# InterfazSpectrum.net
KiCad netlist of a schematic drawn in EAGLE
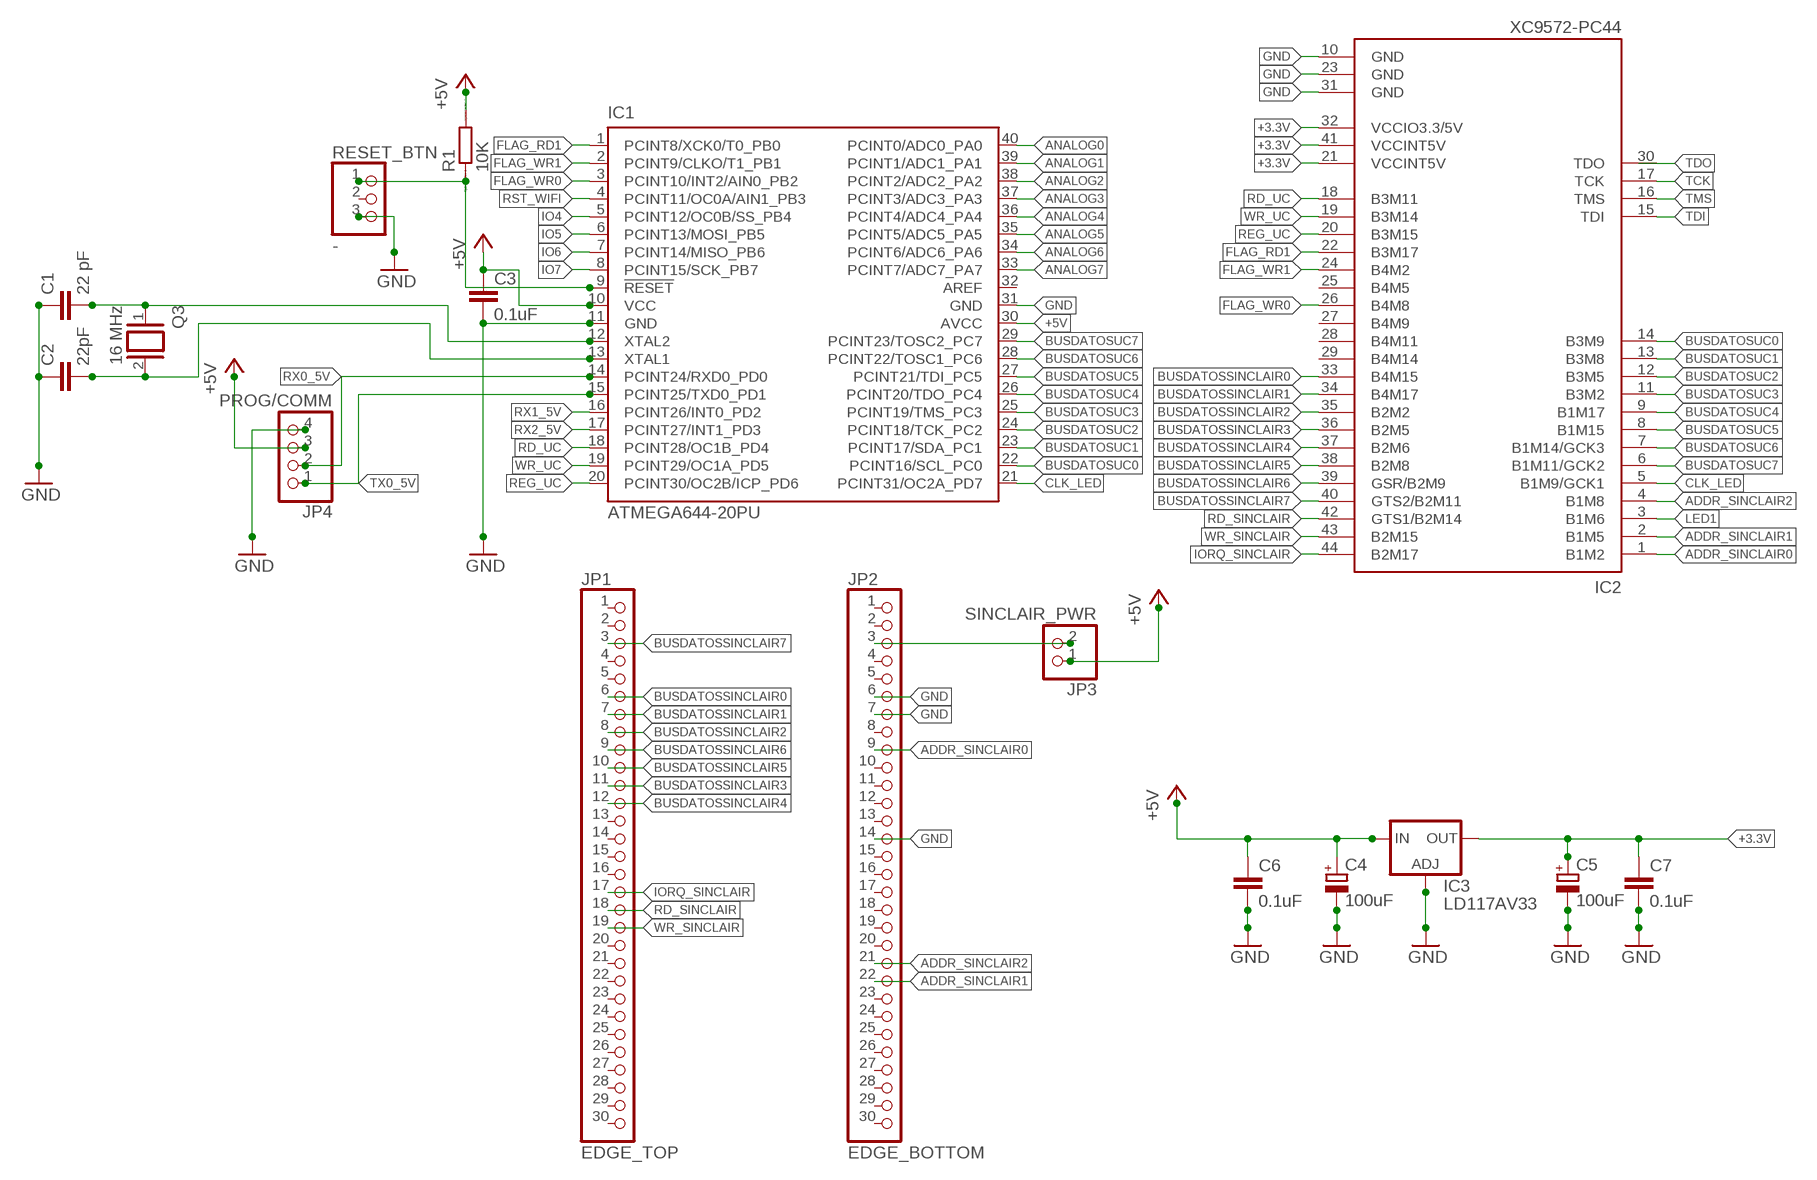
[diagram p0: schematic, sheet 1]

(export (version "E")
  (design (tool "Eeschema 10.0.6"))
  (components
    (comp (ref "C1")
      (value "22 pF")
      (footprint "eagle-import:C025-024X044")
      (libsource (lib "eagle-import") (part "C-EU025-024X044"))
    )
    (comp (ref "C2")
      (value "22pF")
      (footprint "eagle-import:C025-024X044")
      (libsource (lib "eagle-import") (part "C-EU025-024X044"))
    )
    (comp (ref "C3")
      (value "0.1uF")
      (footprint "eagle-import:C025-025X050")
      (libsource (lib "eagle-import") (part "C-EU025-025X050"))
    )
    (comp (ref "C4")
      (value "100uF")
      (footprint "eagle-import:E2,5-7")
      (libsource (lib "eagle-import") (part "CPOL-EUE2.5-7"))
    )
    (comp (ref "C5")
      (value "100uF")
      (footprint "eagle-import:E2,5-7")
      (libsource (lib "eagle-import") (part "CPOL-EUE2.5-7"))
    )
    (comp (ref "C6")
      (value "0.1uF")
      (footprint "eagle-import:C025-025X050")
      (libsource (lib "eagle-import") (part "C-EU025-025X050"))
    )
    (comp (ref "C7")
      (value "0.1uF")
      (footprint "eagle-import:C025-025X050")
      (libsource (lib "eagle-import") (part "C-EU025-025X050"))
    )
    (comp (ref "IC1")
      (value "ATMEGA644-20PU")
      (footprint "eagle-import:DIL40")
      (libsource (lib "eagle-import") (part "ATMEGA644-PU20"))
    )
    (comp (ref "IC2")
      (value "XC9572-PC44")
      (footprint "eagle-import:PLCC-S44")
      (libsource (lib "eagle-import") (part "XC9572-PC44"))
    )
    (comp (ref "IC3")
      (value "LD117AV33")
      (footprint "eagle-import:TO220L1")
      (libsource (lib "eagle-import") (part "LD117A?V33"))
    )
    (comp (ref "JP1")
      (value "EDGE_TOP")
      (footprint "eagle-import:1X30")
      (libsource (lib "eagle-import") (part "PINHD-1X30"))
    )
    (comp (ref "JP2")
      (value "EDGE_BOTTOM")
      (footprint "eagle-import:1X30")
      (libsource (lib "eagle-import") (part "PINHD-1X30"))
    )
    (comp (ref "JP3")
      (value "SINCLAIR_PWR")
      (footprint "eagle-import:1X02")
      (libsource (lib "eagle-import") (part "PINHD-1X2"))
    )
    (comp (ref "JP4")
      (value "PROG/COMM")
      (footprint "eagle-import:1X04")
      (libsource (lib "eagle-import") (part "PINHD-1X4"))
    )
    (comp (ref "Q3")
      (value "16 MHz")
      (footprint "eagle-import:QS")
      (libsource (lib "eagle-import") (part "XTAL/S"))
    )
    (comp (ref "R1")
      (value "10K")
      (footprint "eagle-import:0204V")
      (libsource (lib "eagle-import") (part "R-EU_0204_2V"))
    )
    (comp (ref "RESET_BTN")
      (value "-")
      (footprint "eagle-import:1X03")
      (libsource (lib "eagle-import") (part "PINHD-1X3"))
    )
  )
  (nets
    (net (code "1") (name "+3.3V") (class "Default")
      (node (ref "C5") (pin "+") (pinfunction "+_+") (pintype "passive"))
      (node (ref "C7") (pin "1") (pinfunction "1_1") (pintype "passive"))
      (node (ref "IC2") (pin "21") (pinfunction "VCCINT5V_21") (pintype "bidirectional"))
      (node (ref "IC2") (pin "32") (pinfunction "VCCIO3.3/5V_32") (pintype "bidirectional"))
      (node (ref "IC2") (pin "41") (pinfunction "VCCINT5V_41") (pintype "bidirectional"))
      (node (ref "IC3") (pin "2") (pinfunction "OUT_2") (pintype "passive"))
    )
    (net (code "2") (name "+5V") (class "Default")
      (node (ref "C3") (pin "1") (pinfunction "1_1") (pintype "passive"))
      (node (ref "C4") (pin "+") (pinfunction "+_+") (pintype "passive"))
      (node (ref "C6") (pin "1") (pinfunction "1_1") (pintype "passive"))
      (node (ref "IC1") (pin "10") (pinfunction "VCC_10") (pintype "power_in"))
      (node (ref "IC1") (pin "30") (pinfunction "AVCC_30") (pintype "power_in"))
      (node (ref "IC3") (pin "3") (pinfunction "IN_3") (pintype "input"))
      (node (ref "JP3") (pin "1") (pinfunction "1_1") (pintype "passive"))
      (node (ref "JP4") (pin "3") (pinfunction "3_3") (pintype "passive"))
      (node (ref "R1") (pin "2") (pinfunction "2_2") (pintype "passive"))
    )
    (net (code "3") (name "ADDR_SINCLAIR0") (class "Default")
      (node (ref "IC2") (pin "1") (pinfunction "B1M2_1") (pintype "bidirectional"))
      (node (ref "JP2") (pin "9") (pinfunction "9_9") (pintype "passive"))
    )
    (net (code "4") (name "ADDR_SINCLAIR1") (class "Default")
      (node (ref "IC2") (pin "2") (pinfunction "B1M5_2") (pintype "bidirectional"))
      (node (ref "JP2") (pin "22") (pinfunction "22_22") (pintype "passive"))
    )
    (net (code "5") (name "ADDR_SINCLAIR2") (class "Default")
      (node (ref "IC2") (pin "4") (pinfunction "B1M8_4") (pintype "bidirectional"))
      (node (ref "JP2") (pin "21") (pinfunction "21_21") (pintype "passive"))
    )
    (net (code "6") (name "ANALOG0") (class "Default")
      (node (ref "IC1") (pin "40") (pinfunction "PCINT0/ADC0_PA0_40") (pintype "bidirectional"))
    )
    (net (code "7") (name "ANALOG1") (class "Default")
      (node (ref "IC1") (pin "39") (pinfunction "PCINT1/ADC1_PA1_39") (pintype "bidirectional"))
    )
    (net (code "8") (name "ANALOG2") (class "Default")
      (node (ref "IC1") (pin "38") (pinfunction "PCINT2/ADC2_PA2_38") (pintype "bidirectional"))
    )
    (net (code "9") (name "ANALOG3") (class "Default")
      (node (ref "IC1") (pin "37") (pinfunction "PCINT3/ADC3_PA3_37") (pintype "bidirectional"))
    )
    (net (code "10") (name "ANALOG4") (class "Default")
      (node (ref "IC1") (pin "36") (pinfunction "PCINT4/ADC4_PA4_36") (pintype "bidirectional"))
    )
    (net (code "11") (name "ANALOG5") (class "Default")
      (node (ref "IC1") (pin "35") (pinfunction "PCINT5/ADC5_PA5_35") (pintype "bidirectional"))
    )
    (net (code "12") (name "ANALOG6") (class "Default")
      (node (ref "IC1") (pin "34") (pinfunction "PCINT6/ADC6_PA6_34") (pintype "bidirectional"))
    )
    (net (code "13") (name "ANALOG7") (class "Default")
      (node (ref "IC1") (pin "33") (pinfunction "PCINT7/ADC7_PA7_33") (pintype "bidirectional"))
    )
    (net (code "14") (name "BUSDATOSSINCLAIR0") (class "Default")
      (node (ref "IC2") (pin "33") (pinfunction "B4M15_33") (pintype "bidirectional"))
      (node (ref "JP1") (pin "6") (pinfunction "6_6") (pintype "passive"))
    )
    (net (code "15") (name "BUSDATOSSINCLAIR1") (class "Default")
      (node (ref "IC2") (pin "34") (pinfunction "B4M17_34") (pintype "bidirectional"))
      (node (ref "JP1") (pin "7") (pinfunction "7_7") (pintype "passive"))
    )
    (net (code "16") (name "BUSDATOSSINCLAIR2") (class "Default")
      (node (ref "IC2") (pin "35") (pinfunction "B2M2_35") (pintype "bidirectional"))
      (node (ref "JP1") (pin "8") (pinfunction "8_8") (pintype "passive"))
    )
    (net (code "17") (name "BUSDATOSSINCLAIR3") (class "Default")
      (node (ref "IC2") (pin "36") (pinfunction "B2M5_36") (pintype "bidirectional"))
      (node (ref "JP1") (pin "11") (pinfunction "11_11") (pintype "passive"))
    )
    (net (code "18") (name "BUSDATOSSINCLAIR4") (class "Default")
      (node (ref "IC2") (pin "37") (pinfunction "B2M6_37") (pintype "bidirectional"))
      (node (ref "JP1") (pin "12") (pinfunction "12_12") (pintype "passive"))
    )
    (net (code "19") (name "BUSDATOSSINCLAIR5") (class "Default")
      (node (ref "IC2") (pin "38") (pinfunction "B2M8_38") (pintype "bidirectional"))
      (node (ref "JP1") (pin "10") (pinfunction "10_10") (pintype "passive"))
    )
    (net (code "20") (name "BUSDATOSSINCLAIR6") (class "Default")
      (node (ref "IC2") (pin "39") (pinfunction "GSR/B2M9_39") (pintype "bidirectional"))
      (node (ref "JP1") (pin "9") (pinfunction "9_9") (pintype "passive"))
    )
    (net (code "21") (name "BUSDATOSSINCLAIR7") (class "Default")
      (node (ref "IC2") (pin "40") (pinfunction "GTS2/B2M11_40") (pintype "bidirectional"))
      (node (ref "JP1") (pin "3") (pinfunction "3_3") (pintype "passive"))
    )
    (net (code "22") (name "BUSDATOSUC0") (class "Default")
      (node (ref "IC1") (pin "22") (pinfunction "PCINT16/SCL_PC0_22") (pintype "bidirectional"))
      (node (ref "IC2") (pin "14") (pinfunction "B3M9_14") (pintype "bidirectional"))
    )
    (net (code "23") (name "BUSDATOSUC1") (class "Default")
      (node (ref "IC1") (pin "23") (pinfunction "PCINT17/SDA_PC1_23") (pintype "bidirectional"))
      (node (ref "IC2") (pin "13") (pinfunction "B3M8_13") (pintype "bidirectional"))
    )
    (net (code "24") (name "BUSDATOSUC2") (class "Default")
      (node (ref "IC1") (pin "24") (pinfunction "PCINT18/TCK_PC2_24") (pintype "bidirectional"))
      (node (ref "IC2") (pin "12") (pinfunction "B3M5_12") (pintype "bidirectional"))
    )
    (net (code "25") (name "BUSDATOSUC3") (class "Default")
      (node (ref "IC1") (pin "25") (pinfunction "PCINT19/TMS_PC3_25") (pintype "bidirectional"))
      (node (ref "IC2") (pin "11") (pinfunction "B3M2_11") (pintype "bidirectional"))
    )
    (net (code "26") (name "BUSDATOSUC4") (class "Default")
      (node (ref "IC1") (pin "26") (pinfunction "PCINT20/TDO_PC4_26") (pintype "bidirectional"))
      (node (ref "IC2") (pin "9") (pinfunction "B1M17_9") (pintype "bidirectional"))
    )
    (net (code "27") (name "BUSDATOSUC5") (class "Default")
      (node (ref "IC1") (pin "27") (pinfunction "PCINT21/TDI_PC5_27") (pintype "bidirectional"))
      (node (ref "IC2") (pin "8") (pinfunction "B1M15_8") (pintype "bidirectional"))
    )
    (net (code "28") (name "BUSDATOSUC6") (class "Default")
      (node (ref "IC1") (pin "28") (pinfunction "PCINT22/TOSC1_PC6_28") (pintype "bidirectional"))
      (node (ref "IC2") (pin "7") (pinfunction "B1M14/GCK3_7") (pintype "bidirectional"))
    )
    (net (code "29") (name "BUSDATOSUC7") (class "Default")
      (node (ref "IC1") (pin "29") (pinfunction "PCINT23/TOSC2_PC7_29") (pintype "bidirectional"))
      (node (ref "IC2") (pin "6") (pinfunction "B1M11/GCK2_6") (pintype "bidirectional"))
    )
    (net (code "30") (name "CLK_LED") (class "Default")
      (node (ref "IC1") (pin "21") (pinfunction "PCINT31/OC2A_PD7_21") (pintype "bidirectional"))
      (node (ref "IC2") (pin "5") (pinfunction "B1M9/GCK1_5") (pintype "bidirectional"))
    )
    (net (code "31") (name "FLAG_RD1") (class "Default")
      (node (ref "IC1") (pin "1") (pinfunction "PCINT8/XCK0/T0_PB0_1") (pintype "bidirectional"))
      (node (ref "IC2") (pin "22") (pinfunction "B3M17_22") (pintype "bidirectional"))
    )
    (net (code "32") (name "FLAG_WR0") (class "Default")
      (node (ref "IC1") (pin "3") (pinfunction "PCINT10/INT2/AIN0_PB2_3") (pintype "bidirectional"))
      (node (ref "IC2") (pin "26") (pinfunction "B4M8_26") (pintype "bidirectional"))
    )
    (net (code "33") (name "FLAG_WR1") (class "Default")
      (node (ref "IC1") (pin "2") (pinfunction "PCINT9/CLKO/T1_PB1_2") (pintype "bidirectional"))
      (node (ref "IC2") (pin "24") (pinfunction "B4M2_24") (pintype "bidirectional"))
    )
    (net (code "34") (name "GND") (class "Default")
      (node (ref "C1") (pin "1") (pinfunction "1_1") (pintype "passive"))
      (node (ref "C2") (pin "1") (pinfunction "1_1") (pintype "passive"))
      (node (ref "C3") (pin "2") (pinfunction "2_2") (pintype "passive"))
      (node (ref "C4") (pin "-") (pinfunction "-_-") (pintype "passive"))
      (node (ref "C5") (pin "-") (pinfunction "-_-") (pintype "passive"))
      (node (ref "C6") (pin "2") (pinfunction "2_2") (pintype "passive"))
      (node (ref "C7") (pin "2") (pinfunction "2_2") (pintype "passive"))
      (node (ref "IC1") (pin "11") (pinfunction "GND_11") (pintype "power_in"))
      (node (ref "IC1") (pin "31") (pinfunction "GND_31") (pintype "power_in"))
      (node (ref "IC2") (pin "10") (pinfunction "GND_10") (pintype "bidirectional"))
      (node (ref "IC2") (pin "23") (pinfunction "GND_23") (pintype "bidirectional"))
      (node (ref "IC2") (pin "31") (pinfunction "GND_31") (pintype "bidirectional"))
      (node (ref "IC3") (pin "1") (pinfunction "ADJ_1") (pintype "input"))
      (node (ref "JP2") (pin "14") (pinfunction "14_14") (pintype "passive"))
      (node (ref "JP2") (pin "6") (pinfunction "6_6") (pintype "passive"))
      (node (ref "JP2") (pin "7") (pinfunction "7_7") (pintype "passive"))
      (node (ref "JP4") (pin "4") (pinfunction "4_4") (pintype "passive"))
      (node (ref "RESET_BTN") (pin "3") (pinfunction "3_3") (pintype "passive"))
    )
    (net (code "35") (name "IO4") (class "Default")
      (node (ref "IC1") (pin "5") (pinfunction "PCINT12/OC0B/SS_PB4_5") (pintype "bidirectional"))
    )
    (net (code "36") (name "IO5") (class "Default")
      (node (ref "IC1") (pin "6") (pinfunction "PCINT13/MOSI_PB5_6") (pintype "bidirectional"))
    )
    (net (code "37") (name "IO6") (class "Default")
      (node (ref "IC1") (pin "7") (pinfunction "PCINT14/MISO_PB6_7") (pintype "bidirectional"))
    )
    (net (code "38") (name "IO7") (class "Default")
      (node (ref "IC1") (pin "8") (pinfunction "PCINT15/SCK_PB7_8") (pintype "bidirectional"))
    )
    (net (code "39") (name "IORQ_SINCLAIR") (class "Default")
      (node (ref "IC2") (pin "44") (pinfunction "B2M17_44") (pintype "bidirectional"))
      (node (ref "JP1") (pin "17") (pinfunction "17_17") (pintype "passive"))
    )
    (net (code "40") (name "LED1") (class "Default")
      (node (ref "IC2") (pin "3") (pinfunction "B1M6_3") (pintype "bidirectional"))
    )
    (net (code "41") (name "Net-(IC1-XTAL1)") (class "Default")
      (node (ref "C2") (pin "2") (pinfunction "2_2") (pintype "passive"))
      (node (ref "IC1") (pin "13") (pinfunction "XTAL1_13") (pintype "input"))
      (node (ref "Q3") (pin "2") (pinfunction "2_2") (pintype "passive"))
    )
    (net (code "42") (name "Net-(IC1-XTAL2)") (class "Default")
      (node (ref "C1") (pin "2") (pinfunction "2_2") (pintype "passive"))
      (node (ref "IC1") (pin "12") (pinfunction "XTAL2_12") (pintype "output"))
      (node (ref "Q3") (pin "1") (pinfunction "1_1") (pintype "passive"))
    )
    (net (code "43") (name "Net-(IC1-~{RESET})") (class "Default")
      (node (ref "IC1") (pin "9") (pinfunction "~{RESET}_9") (pintype "input"))
      (node (ref "R1") (pin "1") (pinfunction "1_1") (pintype "passive"))
      (node (ref "RESET_BTN") (pin "1") (pinfunction "1_1") (pintype "passive"))
    )
    (net (code "44") (name "Net-(JP2-Pad3)") (class "Default")
      (node (ref "JP2") (pin "3") (pinfunction "3_3") (pintype "passive"))
      (node (ref "JP3") (pin "2") (pinfunction "2_2") (pintype "passive"))
    )
    (net (code "45") (name "RD_SINCLAIR") (class "Default")
      (node (ref "IC2") (pin "42") (pinfunction "GTS1/B2M14_42") (pintype "bidirectional"))
      (node (ref "JP1") (pin "18") (pinfunction "18_18") (pintype "passive"))
    )
    (net (code "46") (name "RD_UC") (class "Default")
      (node (ref "IC1") (pin "18") (pinfunction "PCINT28/OC1B_PD4_18") (pintype "bidirectional"))
      (node (ref "IC2") (pin "18") (pinfunction "B3M11_18") (pintype "bidirectional"))
    )
    (net (code "47") (name "REG_UC") (class "Default")
      (node (ref "IC1") (pin "20") (pinfunction "PCINT30/OC2B/ICP_PD6_20") (pintype "bidirectional"))
      (node (ref "IC2") (pin "20") (pinfunction "B3M15_20") (pintype "bidirectional"))
    )
    (net (code "48") (name "RST_WIFI") (class "Default")
      (node (ref "IC1") (pin "4") (pinfunction "PCINT11/OC0A/AIN1_PB3_4") (pintype "bidirectional"))
    )
    (net (code "49") (name "RX0_5V") (class "Default")
      (node (ref "IC1") (pin "14") (pinfunction "PCINT24/RXD0_PD0_14") (pintype "bidirectional"))
      (node (ref "JP4") (pin "2") (pinfunction "2_2") (pintype "passive"))
    )
    (net (code "50") (name "RX1_5V") (class "Default")
      (node (ref "IC1") (pin "16") (pinfunction "PCINT26/INT0_PD2_16") (pintype "bidirectional"))
    )
    (net (code "51") (name "RX2_5V") (class "Default")
      (node (ref "IC1") (pin "17") (pinfunction "PCINT27/INT1_PD3_17") (pintype "bidirectional"))
    )
    (net (code "52") (name "TCK") (class "Default")
      (node (ref "IC2") (pin "17") (pinfunction "TCK_17") (pintype "bidirectional"))
    )
    (net (code "53") (name "TDI") (class "Default")
      (node (ref "IC2") (pin "15") (pinfunction "TDI_15") (pintype "bidirectional"))
    )
    (net (code "55") (name "TMS") (class "Default")
      (node (ref "IC2") (pin "16") (pinfunction "TMS_16") (pintype "bidirectional"))
    )
    (net (code "56") (name "TX0_5V") (class "Default")
      (node (ref "IC1") (pin "15") (pinfunction "PCINT25/TXD0_PD1_15") (pintype "bidirectional"))
      (node (ref "JP4") (pin "1") (pinfunction "1_1") (pintype "passive"))
    )
    (net (code "57") (name "WR_SINCLAIR") (class "Default")
      (node (ref "IC2") (pin "43") (pinfunction "B2M15_43") (pintype "bidirectional"))
      (node (ref "JP1") (pin "19") (pinfunction "19_19") (pintype "passive"))
    )
    (net (code "58") (name "WR_UC") (class "Default")
      (node (ref "IC1") (pin "19") (pinfunction "PCINT29/OC1A_PD5_19") (pintype "bidirectional"))
      (node (ref "IC2") (pin "19") (pinfunction "B3M14_19") (pintype "bidirectional"))
    )
    (net (code "59") (name "unconnected-(IC1-AREF-Pad32)") (class "Default")
      (node (ref "IC1") (pin "32") (pinfunction "AREF_32") (pintype "passive"))
    )
    (net (code "60") (name "unconnected-(IC2-B4M5-Pad25)") (class "Default")
      (node (ref "IC2") (pin "25") (pinfunction "B4M5_25") (pintype "bidirectional"))
    )
    (net (code "61") (name "unconnected-(IC2-B4M9-Pad27)") (class "Default")
      (node (ref "IC2") (pin "27") (pinfunction "B4M9_27") (pintype "bidirectional"))
    )
    (net (code "62") (name "unconnected-(IC2-B4M11-Pad28)") (class "Default")
      (node (ref "IC2") (pin "28") (pinfunction "B4M11_28") (pintype "bidirectional"))
    )
    (net (code "63") (name "unconnected-(IC2-B4M14-Pad29)") (class "Default")
      (node (ref "IC2") (pin "29") (pinfunction "B4M14_29") (pintype "bidirectional"))
    )
    (net (code "64") (name "unconnected-(IC2-TDO-Pad30)") (class "Default")
      (node (ref "IC2") (pin "30") (pinfunction "TDO_30") (pintype "bidirectional"))
    )
    (net (code "65") (name "unconnected-(JP1-Pad1)") (class "Default")
      (node (ref "JP1") (pin "1") (pinfunction "1_1") (pintype "passive"))
    )
    (net (code "66") (name "unconnected-(JP1-Pad2)") (class "Default")
      (node (ref "JP1") (pin "2") (pinfunction "2_2") (pintype "passive"))
    )
    (net (code "67") (name "unconnected-(JP1-Pad4)") (class "Default")
      (node (ref "JP1") (pin "4") (pinfunction "4_4") (pintype "passive"))
    )
    (net (code "68") (name "unconnected-(JP1-Pad5)") (class "Default")
      (node (ref "JP1") (pin "5") (pinfunction "5_5") (pintype "passive"))
    )
    (net (code "69") (name "unconnected-(JP1-Pad13)") (class "Default")
      (node (ref "JP1") (pin "13") (pinfunction "13_13") (pintype "passive"))
    )
    (net (code "70") (name "unconnected-(JP1-Pad14)") (class "Default")
      (node (ref "JP1") (pin "14") (pinfunction "14_14") (pintype "passive"))
    )
    (net (code "71") (name "unconnected-(JP1-Pad15)") (class "Default")
      (node (ref "JP1") (pin "15") (pinfunction "15_15") (pintype "passive"))
    )
    (net (code "72") (name "unconnected-(JP1-Pad16)") (class "Default")
      (node (ref "JP1") (pin "16") (pinfunction "16_16") (pintype "passive"))
    )
    (net (code "73") (name "unconnected-(JP1-Pad20)") (class "Default")
      (node (ref "JP1") (pin "20") (pinfunction "20_20") (pintype "passive"))
    )
    (net (code "74") (name "unconnected-(JP1-Pad21)") (class "Default")
      (node (ref "JP1") (pin "21") (pinfunction "21_21") (pintype "passive"))
    )
    (net (code "75") (name "unconnected-(JP1-Pad22)") (class "Default")
      (node (ref "JP1") (pin "22") (pinfunction "22_22") (pintype "passive"))
    )
    (net (code "76") (name "unconnected-(JP1-Pad23)") (class "Default")
      (node (ref "JP1") (pin "23") (pinfunction "23_23") (pintype "passive"))
    )
    (net (code "77") (name "unconnected-(JP1-Pad24)") (class "Default")
      (node (ref "JP1") (pin "24") (pinfunction "24_24") (pintype "passive"))
    )
    (net (code "78") (name "unconnected-(JP1-Pad25)") (class "Default")
      (node (ref "JP1") (pin "25") (pinfunction "25_25") (pintype "passive"))
    )
    (net (code "79") (name "unconnected-(JP1-Pad26)") (class "Default")
      (node (ref "JP1") (pin "26") (pinfunction "26_26") (pintype "passive"))
    )
    (net (code "80") (name "unconnected-(JP1-Pad27)") (class "Default")
      (node (ref "JP1") (pin "27") (pinfunction "27_27") (pintype "passive"))
    )
    (net (code "81") (name "unconnected-(JP1-Pad28)") (class "Default")
      (node (ref "JP1") (pin "28") (pinfunction "28_28") (pintype "passive"))
    )
    (net (code "82") (name "unconnected-(JP1-Pad29)") (class "Default")
      (node (ref "JP1") (pin "29") (pinfunction "29_29") (pintype "passive"))
    )
    (net (code "83") (name "unconnected-(JP1-Pad30)") (class "Default")
      (node (ref "JP1") (pin "30") (pinfunction "30_30") (pintype "passive"))
    )
    (net (code "84") (name "unconnected-(JP2-Pad1)") (class "Default")
      (node (ref "JP2") (pin "1") (pinfunction "1_1") (pintype "passive"))
    )
    (net (code "85") (name "unconnected-(JP2-Pad2)") (class "Default")
      (node (ref "JP2") (pin "2") (pinfunction "2_2") (pintype "passive"))
    )
    (net (code "86") (name "unconnected-(JP2-Pad4)") (class "Default")
      (node (ref "JP2") (pin "4") (pinfunction "4_4") (pintype "passive"))
    )
    (net (code "87") (name "unconnected-(JP2-Pad5)") (class "Default")
      (node (ref "JP2") (pin "5") (pinfunction "5_5") (pintype "passive"))
    )
    (net (code "88") (name "unconnected-(JP2-Pad8)") (class "Default")
      (node (ref "JP2") (pin "8") (pinfunction "8_8") (pintype "passive"))
    )
    (net (code "89") (name "unconnected-(JP2-Pad10)") (class "Default")
      (node (ref "JP2") (pin "10") (pinfunction "10_10") (pintype "passive"))
    )
    (net (code "90") (name "unconnected-(JP2-Pad11)") (class "Default")
      (node (ref "JP2") (pin "11") (pinfunction "11_11") (pintype "passive"))
    )
    (net (code "91") (name "unconnected-(JP2-Pad12)") (class "Default")
      (node (ref "JP2") (pin "12") (pinfunction "12_12") (pintype "passive"))
    )
    (net (code "92") (name "unconnected-(JP2-Pad13)") (class "Default")
      (node (ref "JP2") (pin "13") (pinfunction "13_13") (pintype "passive"))
    )
    (net (code "93") (name "unconnected-(JP2-Pad15)") (class "Default")
      (node (ref "JP2") (pin "15") (pinfunction "15_15") (pintype "passive"))
    )
    (net (code "94") (name "unconnected-(JP2-Pad16)") (class "Default")
      (node (ref "JP2") (pin "16") (pinfunction "16_16") (pintype "passive"))
    )
    (net (code "95") (name "unconnected-(JP2-Pad17)") (class "Default")
      (node (ref "JP2") (pin "17") (pinfunction "17_17") (pintype "passive"))
    )
    (net (code "96") (name "unconnected-(JP2-Pad18)") (class "Default")
      (node (ref "JP2") (pin "18") (pinfunction "18_18") (pintype "passive"))
    )
    (net (code "97") (name "unconnected-(JP2-Pad19)") (class "Default")
      (node (ref "JP2") (pin "19") (pinfunction "19_19") (pintype "passive"))
    )
    (net (code "98") (name "unconnected-(JP2-Pad20)") (class "Default")
      (node (ref "JP2") (pin "20") (pinfunction "20_20") (pintype "passive"))
    )
    (net (code "99") (name "unconnected-(JP2-Pad23)") (class "Default")
      (node (ref "JP2") (pin "23") (pinfunction "23_23") (pintype "passive"))
    )
    (net (code "100") (name "unconnected-(JP2-Pad24)") (class "Default")
      (node (ref "JP2") (pin "24") (pinfunction "24_24") (pintype "passive"))
    )
    (net (code "101") (name "unconnected-(JP2-Pad25)") (class "Default")
      (node (ref "JP2") (pin "25") (pinfunction "25_25") (pintype "passive"))
    )
    (net (code "102") (name "unconnected-(JP2-Pad26)") (class "Default")
      (node (ref "JP2") (pin "26") (pinfunction "26_26") (pintype "passive"))
    )
    (net (code "103") (name "unconnected-(JP2-Pad27)") (class "Default")
      (node (ref "JP2") (pin "27") (pinfunction "27_27") (pintype "passive"))
    )
    (net (code "104") (name "unconnected-(JP2-Pad28)") (class "Default")
      (node (ref "JP2") (pin "28") (pinfunction "28_28") (pintype "passive"))
    )
    (net (code "105") (name "unconnected-(JP2-Pad29)") (class "Default")
      (node (ref "JP2") (pin "29") (pinfunction "29_29") (pintype "passive"))
    )
    (net (code "106") (name "unconnected-(JP2-Pad30)") (class "Default")
      (node (ref "JP2") (pin "30") (pinfunction "30_30") (pintype "passive"))
    )
    (net (code "107") (name "unconnected-(RESET_BTN-Pad2)") (class "Default")
      (node (ref "RESET_BTN") (pin "2") (pinfunction "2_2") (pintype "passive"))
    )
  )
)
